# HV_Wiring.net
KiCad netlist of a schematic drawn in EAGLE
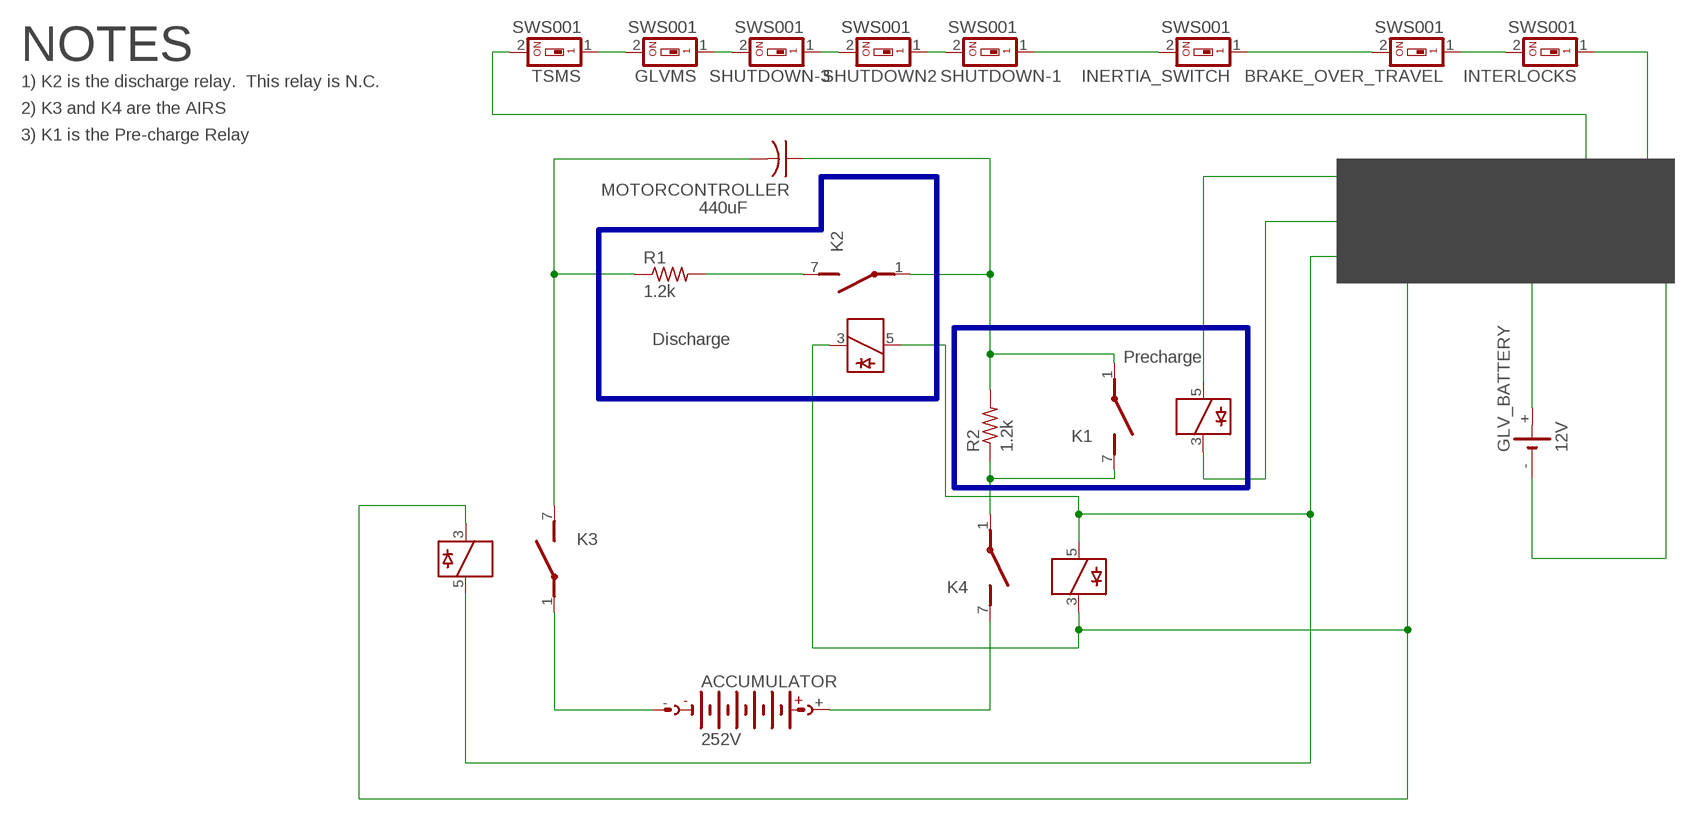
[diagram p0: schematic, sheet 1]

(export (version "E")
  (design (tool "Eeschema 10.0.6"))
  (components
    (comp (ref "ACCUMULATOR")
      (value "252V")
      (footprint "eagle-import:AB9V")
      (libsource (lib "eagle-import") (part "AB9V"))
    )
    (comp (ref "BRAKE_OVER_TRAVEL")
      (value "SWS001")
      (footprint "eagle-import:SMS-001")
      (libsource (lib "eagle-import") (part "SWS001"))
    )
    (comp (ref "GLVMS")
      (value "SWS001")
      (footprint "eagle-import:SMS-001")
      (libsource (lib "eagle-import") (part "SWS001"))
    )
    (comp (ref "GLV_BATTERY")
      (value "12V")
      (footprint "eagle-import:CH291-1220LF")
      (libsource (lib "eagle-import") (part "CH291-1220LF"))
    )
    (comp (ref "INERTIA_SWITCH")
      (value "SWS001")
      (footprint "eagle-import:SMS-001")
      (libsource (lib "eagle-import") (part "SWS001"))
    )
    (comp (ref "INTERLOCKS")
      (value "SWS001")
      (footprint "eagle-import:SMS-001")
      (libsource (lib "eagle-import") (part "SWS001"))
    )
    (comp (ref "K1")
      (value "35701331")
      (footprint "eagle-import:REED")
      (libsource (lib "eagle-import") (part "35701331"))
    )
    (comp (ref "K2")
      (value "35701331")
      (footprint "eagle-import:REED")
      (libsource (lib "eagle-import") (part "35701331"))
    )
    (comp (ref "K3")
      (value "35701331")
      (footprint "eagle-import:REED")
      (libsource (lib "eagle-import") (part "35701331"))
    )
    (comp (ref "K4")
      (value "35701331")
      (footprint "eagle-import:REED")
      (libsource (lib "eagle-import") (part "35701331"))
    )
    (comp (ref "MOTORCONTROLLER")
      (value "440uF")
      (footprint "eagle-import:C025-024X044")
      (libsource (lib "eagle-import") (part "C-US025-024X044"))
    )
    (comp (ref "R1")
      (value "1.2k")
      (footprint "eagle-import:0204V")
      (libsource (lib "eagle-import") (part "R-US_0204/2V"))
    )
    (comp (ref "R2")
      (value "1.2k")
      (footprint "eagle-import:0204V")
      (libsource (lib "eagle-import") (part "R-US_0204/2V"))
    )
    (comp (ref "SHUTDOWN-1")
      (value "SWS001")
      (footprint "eagle-import:SMS-001")
      (libsource (lib "eagle-import") (part "SWS001"))
    )
    (comp (ref "SHUTDOWN-3")
      (value "SWS001")
      (footprint "eagle-import:SMS-001")
      (libsource (lib "eagle-import") (part "SWS001"))
    )
    (comp (ref "SHUTDOWN2")
      (value "SWS001")
      (footprint "eagle-import:SMS-001")
      (libsource (lib "eagle-import") (part "SWS001"))
    )
    (comp (ref "TSMS")
      (value "SWS001")
      (footprint "eagle-import:SMS-001")
      (libsource (lib "eagle-import") (part "SWS001"))
    )
  )
  (nets
    (net (code "1") (name "Net-(BRAKE_OVER_TRAVEL-Pad1)") (class "Default")
      (node (ref "BRAKE_OVER_TRAVEL") (pin "1") (pinfunction "1_1") (pintype "passive"))
      (node (ref "INTERLOCKS") (pin "2") (pinfunction "2_2") (pintype "passive"))
    )
    (net (code "2") (name "Net-(BRAKE_OVER_TRAVEL-Pad2)") (class "Default")
      (node (ref "BRAKE_OVER_TRAVEL") (pin "2") (pinfunction "2_2") (pintype "passive"))
      (node (ref "INERTIA_SWITCH") (pin "1") (pinfunction "1_1") (pintype "passive"))
    )
    (net (code "3") (name "Net-(GLVMS-Pad1)") (class "Default")
      (node (ref "GLVMS") (pin "1") (pinfunction "1_1") (pintype "passive"))
      (node (ref "SHUTDOWN-3") (pin "2") (pinfunction "2_2") (pintype "passive"))
    )
    (net (code "4") (name "Net-(GLVMS-Pad2)") (class "Default")
      (node (ref "GLVMS") (pin "2") (pinfunction "2_2") (pintype "passive"))
      (node (ref "TSMS") (pin "1") (pinfunction "1_1") (pintype "passive"))
    )
    (net (code "5") (name "Net-(INERTIA_SWITCH-Pad2)") (class "Default")
      (node (ref "INERTIA_SWITCH") (pin "2") (pinfunction "2_2") (pintype "passive"))
      (node (ref "SHUTDOWN-1") (pin "1") (pinfunction "1_1") (pintype "passive"))
    )
    (net (code "6") (name "Net-(K1B-P)") (class "Default")
      (node (ref "K1") (pin "1") (pinfunction "P_1") (pintype "passive"))
      (node (ref "K2") (pin "1") (pinfunction "P_1") (pintype "passive"))
      (node (ref "MOTORCONTROLLER") (pin "1") (pinfunction "1_1") (pintype "passive"))
      (node (ref "R2") (pin "2") (pinfunction "2_2") (pintype "passive"))
    )
    (net (code "7") (name "Net-(K1B-S)") (class "Default")
      (node (ref "K1") (pin "7") (pinfunction "S_7") (pintype "passive"))
      (node (ref "K4") (pin "1") (pinfunction "P_1") (pintype "passive"))
      (node (ref "R2") (pin "1") (pinfunction "1_1") (pintype "passive"))
    )
    (net (code "8") (name "Net-(K2-Pad3)") (class "Default")
      (node (ref "K2") (pin "3") (pinfunction "3_3") (pintype "passive"))
      (node (ref "K3") (pin "3") (pinfunction "3_3") (pintype "passive"))
      (node (ref "K4") (pin "3") (pinfunction "3_3") (pintype "passive"))
    )
    (net (code "9") (name "Net-(K2-Pad5)") (class "Default")
      (node (ref "K2") (pin "5") (pinfunction "5_5") (pintype "passive"))
      (node (ref "K3") (pin "5") (pinfunction "5_5") (pintype "passive"))
      (node (ref "K4") (pin "5") (pinfunction "5_5") (pintype "passive"))
    )
    (net (code "10") (name "Net-(K2B-S)") (class "Default")
      (node (ref "K2") (pin "7") (pinfunction "S_7") (pintype "passive"))
      (node (ref "R1") (pin "2") (pinfunction "2_2") (pintype "passive"))
    )
    (net (code "11") (name "Net-(K3B-P)") (class "Default")
      (node (ref "ACCUMULATOR") (pin "-") (pinfunction "-_-") (pintype "passive"))
      (node (ref "K3") (pin "1") (pinfunction "P_1") (pintype "passive"))
    )
    (net (code "12") (name "Net-(K3B-S)") (class "Default")
      (node (ref "K3") (pin "7") (pinfunction "S_7") (pintype "passive"))
      (node (ref "MOTORCONTROLLER") (pin "2") (pinfunction "2_2") (pintype "passive"))
      (node (ref "R1") (pin "1") (pinfunction "1_1") (pintype "passive"))
    )
    (net (code "13") (name "Net-(K4B-S)") (class "Default")
      (node (ref "ACCUMULATOR") (pin "+") (pinfunction "+_+") (pintype "passive"))
      (node (ref "K4") (pin "7") (pinfunction "S_7") (pintype "passive"))
    )
    (net (code "14") (name "Net-(SHUTDOWN-1-Pad2)") (class "Default")
      (node (ref "SHUTDOWN-1") (pin "2") (pinfunction "2_2") (pintype "passive"))
      (node (ref "SHUTDOWN2") (pin "1") (pinfunction "1_1") (pintype "passive"))
    )
    (net (code "15") (name "Net-(SHUTDOWN-3-Pad1)") (class "Default")
      (node (ref "SHUTDOWN-3") (pin "1") (pinfunction "1_1") (pintype "passive"))
      (node (ref "SHUTDOWN2") (pin "2") (pinfunction "2_2") (pintype "passive"))
    )
    (net (code "16") (name "unconnected-(GLV_BATTERY-Pad+)") (class "Default")
      (node (ref "GLV_BATTERY") (pin "+") (pinfunction "+_+") (pintype "passive"))
    )
    (net (code "17") (name "unconnected-(GLV_BATTERY-Pad-)") (class "Default")
      (node (ref "GLV_BATTERY") (pin "-") (pinfunction "-_-") (pintype "passive"))
    )
    (net (code "18") (name "unconnected-(INTERLOCKS-Pad1)") (class "Default")
      (node (ref "INTERLOCKS") (pin "1") (pinfunction "1_1") (pintype "passive"))
    )
    (net (code "19") (name "unconnected-(K1-Pad3)") (class "Default")
      (node (ref "K1") (pin "3") (pinfunction "3_3") (pintype "passive"))
    )
    (net (code "20") (name "unconnected-(K1-Pad5)") (class "Default")
      (node (ref "K1") (pin "5") (pinfunction "5_5") (pintype "passive"))
    )
    (net (code "21") (name "unconnected-(TSMS-Pad2)") (class "Default")
      (node (ref "TSMS") (pin "2") (pinfunction "2_2") (pintype "passive"))
    )
  )
)
